# RF_Amplifier.net
KiCad netlist of a schematic drawn in EasyEDA Pro
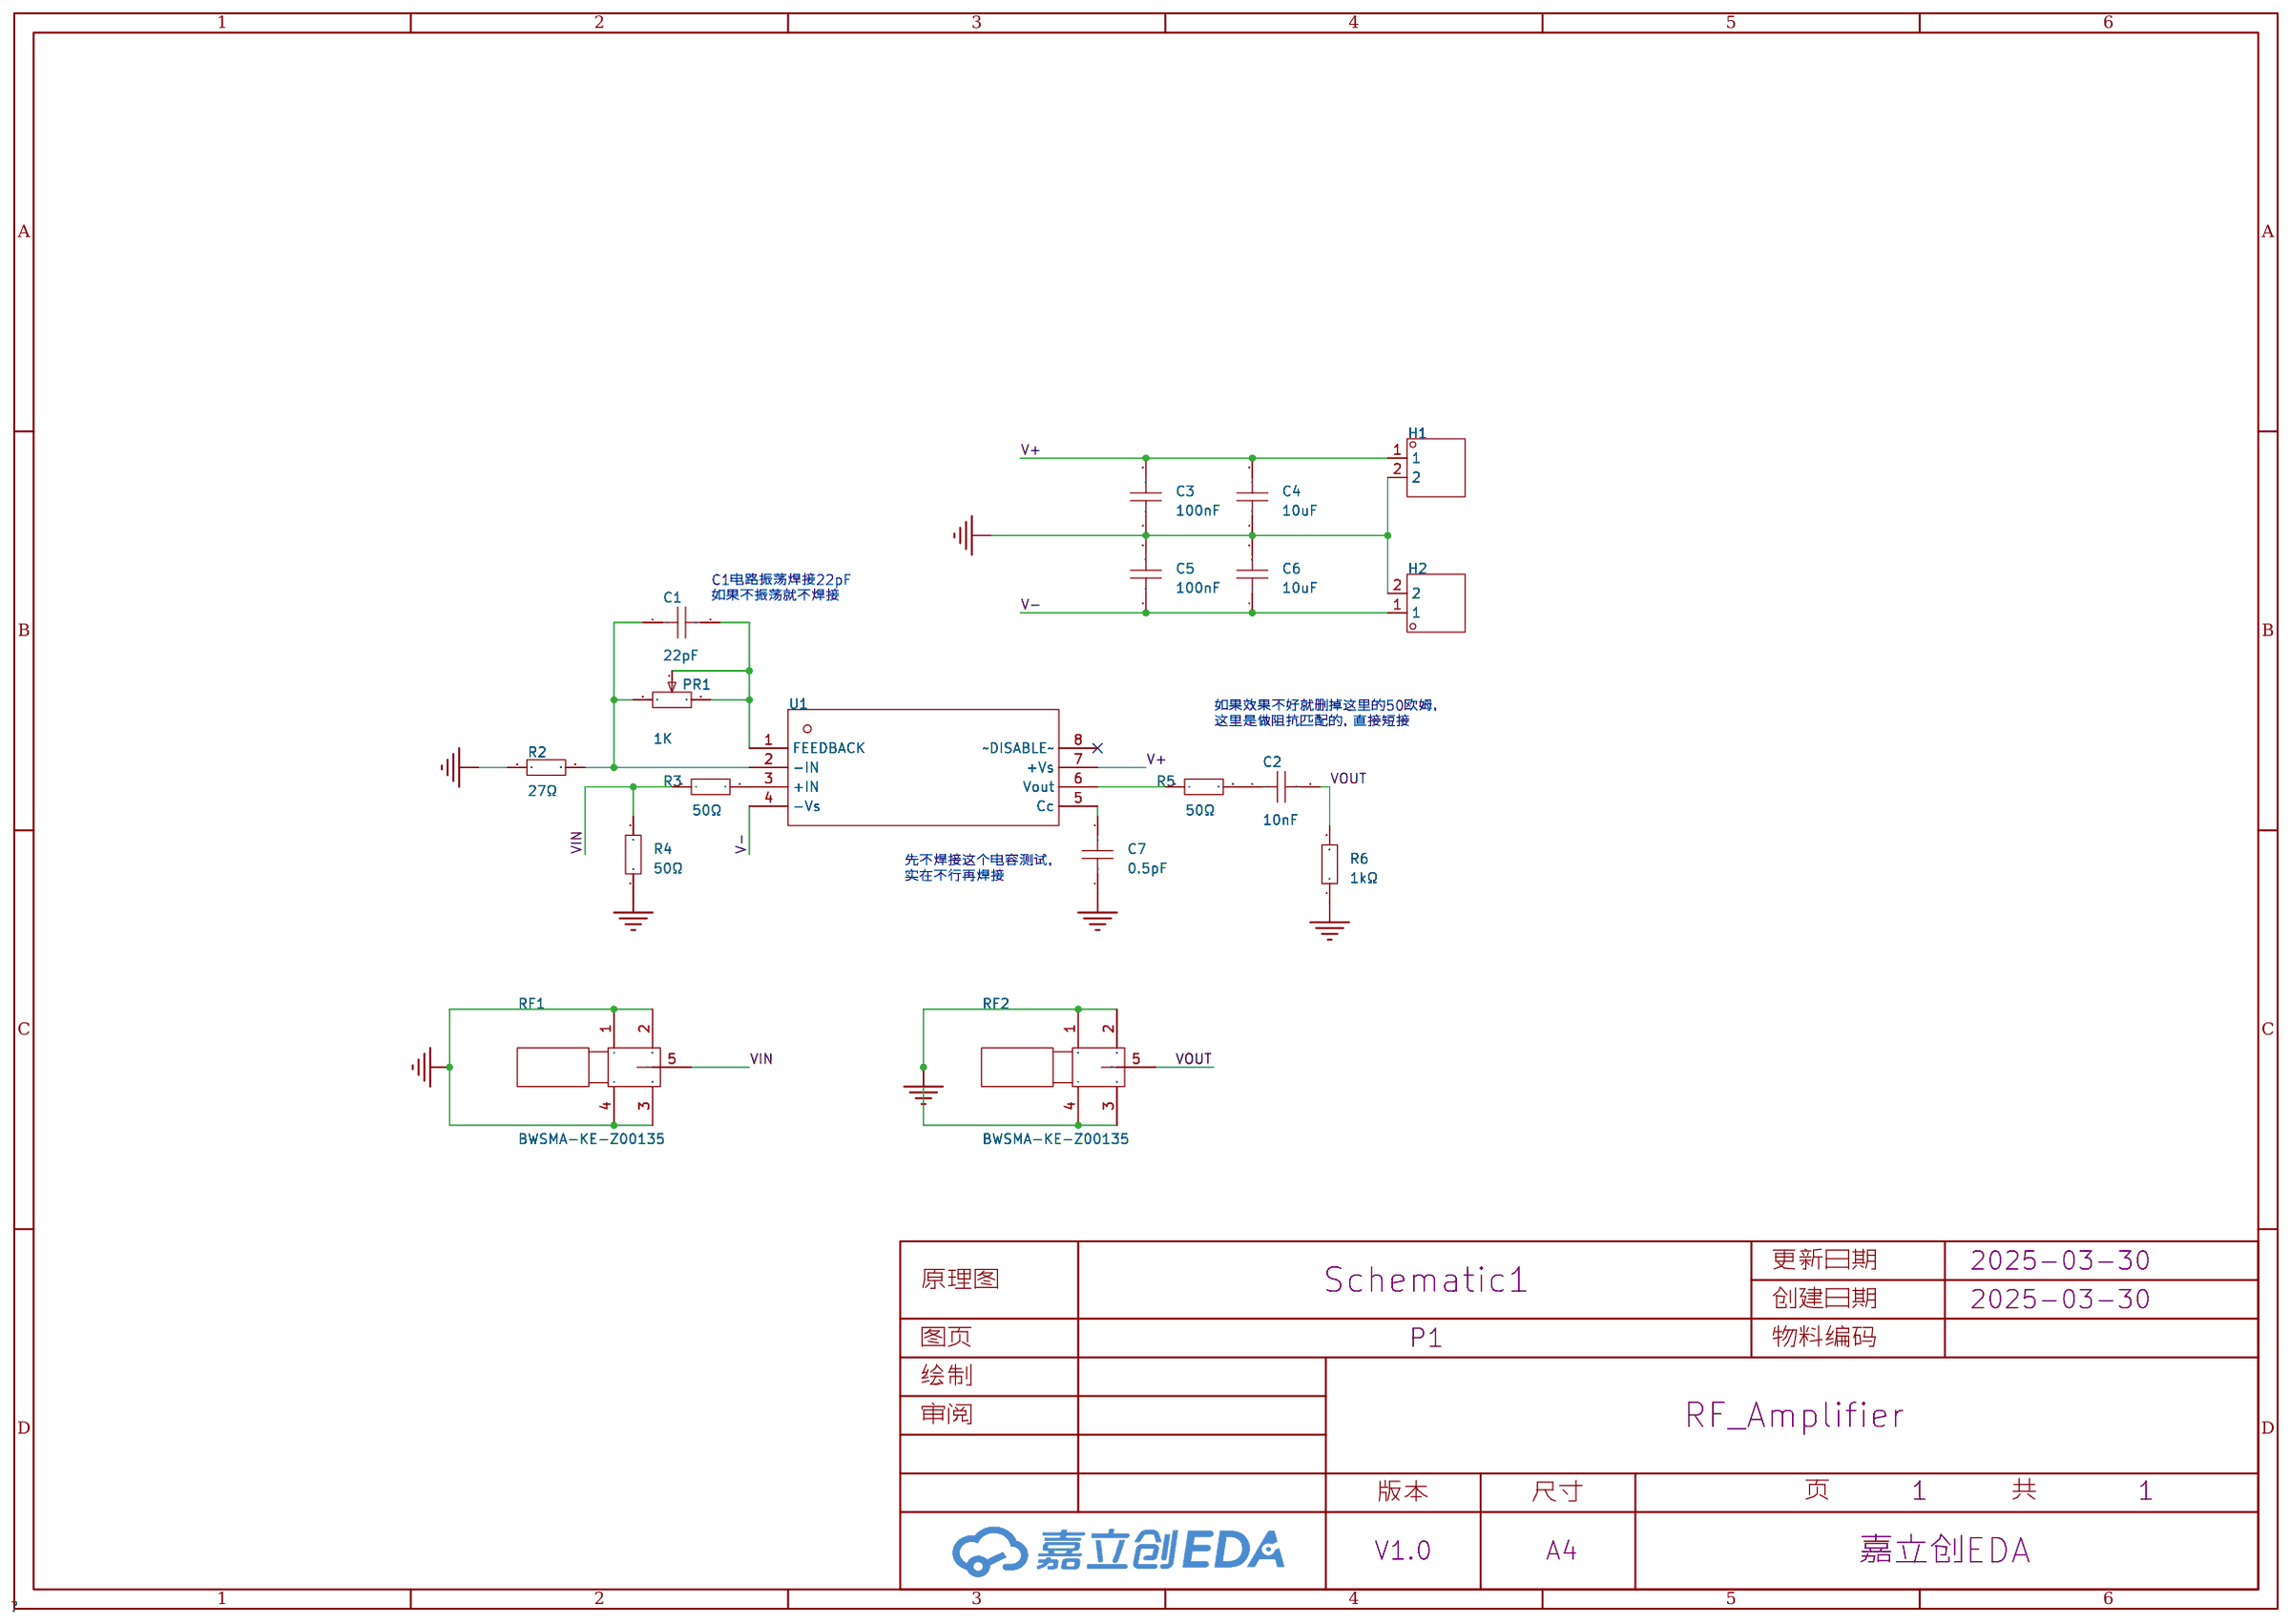
[diagram p0: schematic sheet]

(export (version "E")
  (design (tool "Eeschema 10.0.6"))
  (components
    (comp (ref "C1")
      (value "22pF")
      (footprint "easyedapro:C0603")
      (libsource (lib "easyedapro") (part "CapAcitance"))
    )
    (comp (ref "C2")
      (value "10nF")
      (footprint "easyedapro:C0603")
      (libsource (lib "easyedapro") (part "CapAcitance"))
    )
    (comp (ref "C3")
      (value "100nF")
      (footprint "easyedapro:C0603")
      (libsource (lib "easyedapro") (part "CapAcitance"))
    )
    (comp (ref "C4")
      (value "10uF")
      (footprint "easyedapro:C0603")
      (libsource (lib "easyedapro") (part "CapAcitance"))
    )
    (comp (ref "C5")
      (value "100nF")
      (footprint "easyedapro:C0603")
      (libsource (lib "easyedapro") (part "CapAcitance"))
    )
    (comp (ref "C6")
      (value "10uF")
      (footprint "easyedapro:C0603")
      (libsource (lib "easyedapro") (part "CapAcitance"))
    )
    (comp (ref "C7")
      (value "0.5pF")
      (footprint "easyedapro:C0603")
      (libsource (lib "easyedapro") (part "CapAcitance"))
    )
    (comp (ref "H1")
      (value "~")
      (footprint "easyedapro:HDR-TH_2P-P2.54-V-M-1")
      (libsource (lib "easyedapro") (part "210S-1*2P L=11.6MMGold-plated black"))
    )
    (comp (ref "H2")
      (value "~")
      (footprint "easyedapro:HDR-TH_2P-P2.54-V-M-1")
      (libsource (lib "easyedapro") (part "210S-1*2P L=11.6MMGold-plated black"))
    )
    (comp (ref "PR1")
      (value "1K")
      (footprint "easyedapro:R_3386P")
      (libsource (lib "easyedapro") (part "3386P-1-103LF"))
    )
    (comp (ref "R2") (value "27Ω") (footprint "easyedapro:R0603") (libsource (lib "easyedapro") (part "电阻")))
    (comp (ref "R3") (value "50Ω") (footprint "easyedapro:R0603") (libsource (lib "easyedapro") (part "电阻")))
    (comp (ref "R4") (value "50Ω") (footprint "easyedapro:R0603") (libsource (lib "easyedapro") (part "电阻")))
    (comp (ref "R5") (value "50Ω") (footprint "easyedapro:R0603") (libsource (lib "easyedapro") (part "电阻")))
    (comp (ref "R6") (value "1kΩ") (footprint "easyedapro:R0603") (libsource (lib "easyedapro") (part "电阻")))
    (comp (ref "RF1")
      (value "BWSMA-KE-Z00135")
      (footprint "easyedapro:SMA-TH_BWSMA-KE-Z001")
      (description "SMA-KWE 正脚射频座直插板端座子 RF天线连接座 H13.5MM 连接器类型：板端 射频系列：SMA-KER 频率：6GHz 接口类型：内孔 端口数量：1 产品材质电镀：铜镀金")
      (fields (field (name "Manufacturer") "LX(连欣科技)"))
      (libsource (lib "easyedapro") (part "BWSMA-KE-Z00135"))
    )
    (comp (ref "RF2")
      (value "BWSMA-KE-Z00135")
      (footprint "easyedapro:SMA-TH_BWSMA-KE-Z001")
      (description "SMA-KWE 正脚射频座直插板端座子 RF天线连接座 H13.5MM 连接器类型：板端 射频系列：SMA-KER 频率：6GHz 接口类型：内孔 端口数量：1 产品材质电镀：铜镀金")
      (fields (field (name "Manufacturer") "LX(连欣科技)"))
      (libsource (lib "easyedapro") (part "BWSMA-KE-Z00135"))
    )
    (comp (ref "U1")
      (value "~")
      (footprint "easyedapro:DIP-8_L10.0-W6.5-P2.54-LS7.6-BL-A")
      (libsource (lib "easyedapro") (part "DIP-8"))
    )
  )
  (nets
    (net (code "1") (name "/V+") (class "Default")
      (node (ref "C3") (pin "2") (pinfunction "2_2") (pintype "input"))
      (node (ref "C4") (pin "2") (pinfunction "2_2") (pintype "input"))
      (node (ref "H1") (pin "1") (pinfunction "1_1") (pintype "unspecified"))
      (node (ref "U1") (pin "7") (pinfunction "+Vs_7") (pintype "input"))
    )
    (net (code "2") (name "/V-") (class "Default")
      (node (ref "C5") (pin "1") (pinfunction "1_1") (pintype "input"))
      (node (ref "C6") (pin "1") (pinfunction "1_1") (pintype "input"))
      (node (ref "H2") (pin "1") (pinfunction "1_1") (pintype "unspecified"))
      (node (ref "U1") (pin "4") (pinfunction "-Vs_4") (pintype "input"))
    )
    (net (code "3") (name "/VIN") (class "Default")
      (node (ref "R3") (pin "1") (pinfunction "1_1") (pintype "input"))
      (node (ref "R4") (pin "2") (pinfunction "2_2") (pintype "input"))
      (node (ref "RF1") (pin "5") (pinfunction "5_5") (pintype "unspecified"))
    )
    (net (code "4") (name "/VOUT") (class "Default")
      (node (ref "C2") (pin "2") (pinfunction "2_2") (pintype "input"))
      (node (ref "R6") (pin "2") (pinfunction "2_2") (pintype "input"))
      (node (ref "RF2") (pin "5") (pinfunction "5_5") (pintype "unspecified"))
    )
    (net (code "5") (name "GND") (class "Default")
      (node (ref "C3") (pin "1") (pinfunction "1_1") (pintype "input"))
      (node (ref "C4") (pin "1") (pinfunction "1_1") (pintype "input"))
      (node (ref "C5") (pin "2") (pinfunction "2_2") (pintype "input"))
      (node (ref "C6") (pin "2") (pinfunction "2_2") (pintype "input"))
      (node (ref "C7") (pin "1") (pinfunction "1_1") (pintype "input"))
      (node (ref "H1") (pin "2") (pinfunction "2_2") (pintype "unspecified"))
      (node (ref "H2") (pin "2") (pinfunction "2_2") (pintype "unspecified"))
      (node (ref "R2") (pin "1") (pinfunction "1_1") (pintype "input"))
      (node (ref "R4") (pin "1") (pinfunction "1_1") (pintype "input"))
      (node (ref "R6") (pin "1") (pinfunction "1_1") (pintype "input"))
      (node (ref "RF1") (pin "1") (pinfunction "1_1") (pintype "unspecified"))
      (node (ref "RF1") (pin "2") (pinfunction "2_2") (pintype "unspecified"))
      (node (ref "RF1") (pin "3") (pinfunction "3_3") (pintype "unspecified"))
      (node (ref "RF1") (pin "4") (pinfunction "4_4") (pintype "unspecified"))
      (node (ref "RF2") (pin "1") (pinfunction "1_1") (pintype "unspecified"))
      (node (ref "RF2") (pin "2") (pinfunction "2_2") (pintype "unspecified"))
      (node (ref "RF2") (pin "3") (pinfunction "3_3") (pintype "unspecified"))
      (node (ref "RF2") (pin "4") (pinfunction "4_4") (pintype "unspecified"))
    )
    (net (code "6") (name "Net-(C2-Pad1)") (class "Default")
      (node (ref "C2") (pin "1") (pinfunction "1_1") (pintype "input"))
      (node (ref "R5") (pin "2") (pinfunction "2_2") (pintype "input"))
    )
    (net (code "7") (name "Net-(U1-+IN)") (class "Default")
      (node (ref "R3") (pin "2") (pinfunction "2_2") (pintype "input"))
      (node (ref "U1") (pin "3") (pinfunction "+IN_3") (pintype "input"))
    )
    (net (code "8") (name "Net-(U1--IN)") (class "Default")
      (node (ref "C1") (pin "1") (pinfunction "1_1") (pintype "input"))
      (node (ref "PR1") (pin "3") (pinfunction "3_3") (pintype "input"))
      (node (ref "R2") (pin "2") (pinfunction "2_2") (pintype "input"))
      (node (ref "U1") (pin "2") (pinfunction "-IN_2") (pintype "input"))
    )
    (net (code "9") (name "Net-(U1-Cc)") (class "Default")
      (node (ref "C7") (pin "2") (pinfunction "2_2") (pintype "input"))
      (node (ref "U1") (pin "5") (pinfunction "Cc_5") (pintype "input"))
    )
    (net (code "10") (name "Net-(U1-FEEDBACK)") (class "Default")
      (node (ref "C1") (pin "2") (pinfunction "2_2") (pintype "input"))
      (node (ref "PR1") (pin "1") (pinfunction "1_1") (pintype "input"))
      (node (ref "PR1") (pin "2") (pinfunction "2_2") (pintype "input"))
      (node (ref "U1") (pin "1") (pinfunction "FEEDBACK_1") (pintype "input"))
    )
    (net (code "11") (name "Net-(U1-Vout)") (class "Default")
      (node (ref "R5") (pin "1") (pinfunction "1_1") (pintype "input"))
      (node (ref "U1") (pin "6") (pinfunction "Vout_6") (pintype "input"))
    )
    (net (code "12") (name "unconnected-(U1-~DISABLE~-Pad8)") (class "Default")
      (node (ref "U1") (pin "8") (pinfunction "~DISABLE~_8") (pintype "input+no_connect"))
    )
  )
)
